# ESP.net
KiCad netlist of a schematic drawn in EAGLE
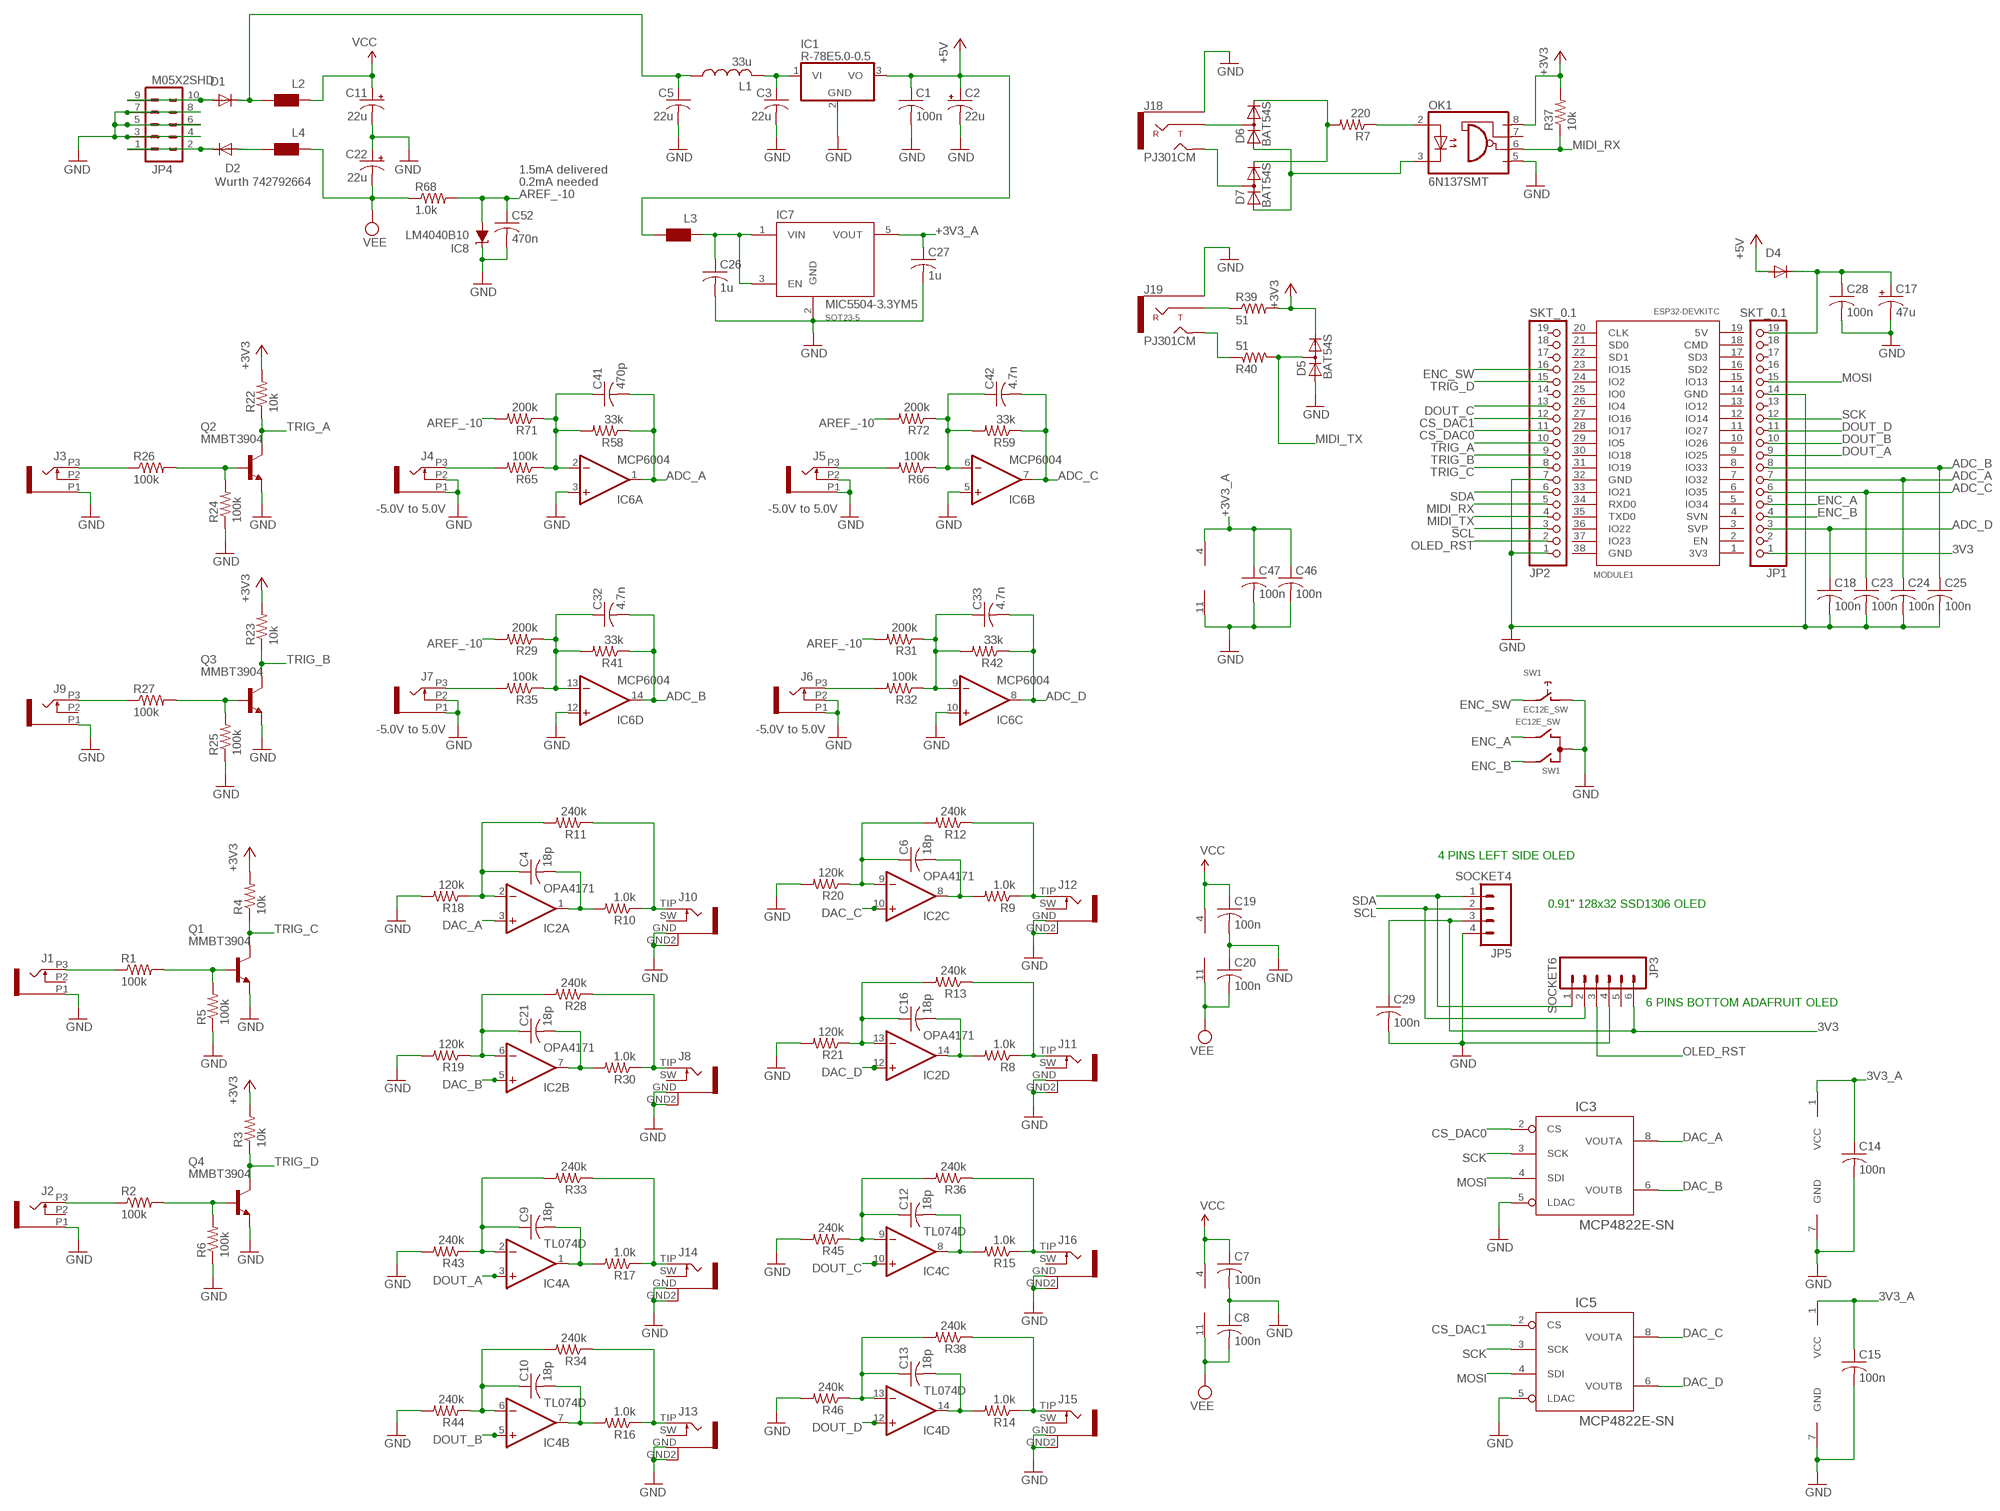
[diagram p0: schematic, sheet 1]

(export (version "E")
  (design (tool "Eeschema 10.0.6"))
  (components
    (comp (ref "C1")
      (value "100n")
      (footprint "eagle-import:C0402")
      (libsource (lib "eagle-import") (part "C-USC0402"))
    )
    (comp (ref "C2")
      (value "22u")
      (footprint "eagle-import:PANASONIC_C")
      (libsource (lib "eagle-import") (part "CPOL-USC"))
    )
    (comp (ref "C3")
      (value "22u")
      (footprint "eagle-import:C1206")
      (libsource (lib "eagle-import") (part "C-USC1206"))
    )
    (comp (ref "C4")
      (value "18p")
      (footprint "eagle-import:C0603")
      (libsource (lib "eagle-import") (part "C-USC0603"))
    )
    (comp (ref "C5")
      (value "22u")
      (footprint "eagle-import:C1206")
      (libsource (lib "eagle-import") (part "C-USC1206"))
    )
    (comp (ref "C6")
      (value "18p")
      (footprint "eagle-import:C0603")
      (libsource (lib "eagle-import") (part "C-USC0603"))
    )
    (comp (ref "C7")
      (value "100n")
      (footprint "eagle-import:C0603")
      (libsource (lib "eagle-import") (part "C-USC0603"))
    )
    (comp (ref "C8")
      (value "100n")
      (footprint "eagle-import:C0603")
      (libsource (lib "eagle-import") (part "C-USC0603"))
    )
    (comp (ref "C9")
      (value "18p")
      (footprint "eagle-import:C0603")
      (libsource (lib "eagle-import") (part "C-USC0603"))
    )
    (comp (ref "C10")
      (value "18p")
      (footprint "eagle-import:C0603")
      (libsource (lib "eagle-import") (part "C-USC0603"))
    )
    (comp (ref "C11")
      (value "22u")
      (footprint "eagle-import:PANASONIC_C")
      (libsource (lib "eagle-import") (part "CPOL-USC"))
    )
    (comp (ref "C12")
      (value "18p")
      (footprint "eagle-import:C0603")
      (libsource (lib "eagle-import") (part "C-USC0603"))
    )
    (comp (ref "C13")
      (value "18p")
      (footprint "eagle-import:C0603")
      (libsource (lib "eagle-import") (part "C-USC0603"))
    )
    (comp (ref "C14")
      (value "100n")
      (footprint "eagle-import:C0603")
      (libsource (lib "eagle-import") (part "C-USC0603"))
    )
    (comp (ref "C15")
      (value "100n")
      (footprint "eagle-import:C0603")
      (libsource (lib "eagle-import") (part "C-USC0603"))
    )
    (comp (ref "C16")
      (value "18p")
      (footprint "eagle-import:C0603")
      (libsource (lib "eagle-import") (part "C-USC0603"))
    )
    (comp (ref "C17")
      (value "47u")
      (footprint "eagle-import:PANASONIC_D")
      (libsource (lib "eagle-import") (part "CPOL-USD"))
    )
    (comp (ref "C18")
      (value "100n")
      (footprint "eagle-import:C0402")
      (libsource (lib "eagle-import") (part "C-USC0402"))
    )
    (comp (ref "C19")
      (value "100n")
      (footprint "eagle-import:C0603")
      (libsource (lib "eagle-import") (part "C-USC0603"))
    )
    (comp (ref "C20")
      (value "100n")
      (footprint "eagle-import:C0603")
      (libsource (lib "eagle-import") (part "C-USC0603"))
    )
    (comp (ref "C21")
      (value "18p")
      (footprint "eagle-import:C0603")
      (libsource (lib "eagle-import") (part "C-USC0603"))
    )
    (comp (ref "C22")
      (value "22u")
      (footprint "eagle-import:PANASONIC_C")
      (libsource (lib "eagle-import") (part "CPOL-USC"))
    )
    (comp (ref "C23")
      (value "100n")
      (footprint "eagle-import:C0402")
      (libsource (lib "eagle-import") (part "C-USC0402"))
    )
    (comp (ref "C24")
      (value "100n")
      (footprint "eagle-import:C0402")
      (libsource (lib "eagle-import") (part "C-USC0402"))
    )
    (comp (ref "C25")
      (value "100n")
      (footprint "eagle-import:C0402")
      (libsource (lib "eagle-import") (part "C-USC0402"))
    )
    (comp (ref "C26")
      (value "1u")
      (footprint "eagle-import:C0603")
      (libsource (lib "eagle-import") (part "C-USC0603"))
    )
    (comp (ref "C27")
      (value "1u")
      (footprint "eagle-import:C0603")
      (libsource (lib "eagle-import") (part "C-USC0603"))
    )
    (comp (ref "C28")
      (value "100n")
      (footprint "eagle-import:C0402")
      (libsource (lib "eagle-import") (part "C-USC0402"))
    )
    (comp (ref "C29")
      (value "100n")
      (footprint "eagle-import:C0603")
      (libsource (lib "eagle-import") (part "C-USC0603"))
    )
    (comp (ref "C32")
      (value "4.7n")
      (footprint "eagle-import:C0402")
      (libsource (lib "eagle-import") (part "C-USC0402"))
    )
    (comp (ref "C33")
      (value "4.7n")
      (footprint "eagle-import:C0402")
      (libsource (lib "eagle-import") (part "C-USC0402"))
    )
    (comp (ref "C41")
      (value "470p")
      (footprint "eagle-import:C0402")
      (libsource (lib "eagle-import") (part "C-USC0402"))
    )
    (comp (ref "C42")
      (value "4.7n")
      (footprint "eagle-import:C0402")
      (libsource (lib "eagle-import") (part "C-USC0402"))
    )
    (comp (ref "C46")
      (value "100n")
      (footprint "eagle-import:C0402")
      (libsource (lib "eagle-import") (part "C-USC0402"))
    )
    (comp (ref "C47")
      (value "100n")
      (footprint "eagle-import:C0402")
      (libsource (lib "eagle-import") (part "C-USC0402"))
    )
    (comp (ref "C52")
      (value "470n")
      (footprint "eagle-import:C0402")
      (libsource (lib "eagle-import") (part "C-USC0402"))
    )
    (comp (ref "D1")
      (value "1N5819HW")
      (footprint "eagle-import:SOD123")
      (libsource (lib "eagle-import") (part "DIODE-SOD123"))
    )
    (comp (ref "D2")
      (value "1N5819HW")
      (footprint "eagle-import:SOD123")
      (libsource (lib "eagle-import") (part "DIODE-SOD123"))
    )
    (comp (ref "D4")
      (value "1N5819HW")
      (footprint "eagle-import:SOD123")
      (libsource (lib "eagle-import") (part "DIODE-SOD123"))
    )
    (comp (ref "D5")
      (value "BAT54S")
      (footprint "eagle-import:SOT23")
      (libsource (lib "eagle-import") (part "DIODE_2CACA-SOT23"))
    )
    (comp (ref "D6")
      (value "BAT54S")
      (footprint "eagle-import:SOT23")
      (libsource (lib "eagle-import") (part "DIODE_2CACA-SOT23"))
    )
    (comp (ref "D7")
      (value "BAT54S")
      (footprint "eagle-import:SOT23")
      (libsource (lib "eagle-import") (part "DIODE_2CACA-SOT23"))
    )
    (comp (ref "IC1")
      (value "R-78E5.0-0.5")
      (footprint "eagle-import:WE78")
      (libsource (lib "eagle-import") (part "WE173950378"))
    )
    (comp (ref "IC2")
      (value "OPA4171")
      (footprint "eagle-import:SO14")
      (libsource (lib "eagle-import") (part "TL074D"))
    )
    (comp (ref "IC3")
      (value "MCP4822E-SN")
      (footprint "eagle-import:SOIC-8")
      (libsource (lib "eagle-import") (part "MCP42E-SN82"))
    )
    (comp (ref "IC4")
      (value "TL074D")
      (footprint "eagle-import:SO14")
      (libsource (lib "eagle-import") (part "TL074D"))
    )
    (comp (ref "IC5")
      (value "MCP4822E-SN")
      (footprint "eagle-import:SOIC-8")
      (libsource (lib "eagle-import") (part "MCP42E-SN82"))
    )
    (comp (ref "IC6")
      (value "MCP6004")
      (footprint "eagle-import:TSSOP14_065")
      (libsource (lib "eagle-import") (part "TL074PW"))
    )
    (comp (ref "IC7")
      (value "MIC5504-3.3YM5")
      (footprint "eagle-import:SOT23-5-DBV")
      (libsource (lib "eagle-import") (part "MIC550X-YM5"))
    )
    (comp (ref "IC8")
      (value "LM4040B10")
      (footprint "eagle-import:DBZ_R-PDSO-G3")
      (fields (field (name "MPN") "LM4041B12IDBZR"))
      (libsource (lib "eagle-import") (part "LM4041DBZB12"))
    )
    (comp (ref "J1")
      (value "PJ301_THONKICONN6")
      (footprint "eagle-import:WQP_PJ_301M6")
      (libsource (lib "eagle-import") (part "PJ301_THONKICONN6"))
    )
    (comp (ref "J2")
      (value "PJ301_THONKICONN6")
      (footprint "eagle-import:WQP_PJ_301M6")
      (libsource (lib "eagle-import") (part "PJ301_THONKICONN6"))
    )
    (comp (ref "J3")
      (value "PJ301_THONKICONN6")
      (footprint "eagle-import:WQP_PJ_301M6")
      (libsource (lib "eagle-import") (part "PJ301_THONKICONN6"))
    )
    (comp (ref "J4")
      (value "PJ301_THONKICONN6")
      (footprint "eagle-import:WQP_PJ_301M6")
      (libsource (lib "eagle-import") (part "PJ301_THONKICONN6"))
    )
    (comp (ref "J5")
      (value "PJ301_THONKICONN6")
      (footprint "eagle-import:WQP_PJ_301M6")
      (libsource (lib "eagle-import") (part "PJ301_THONKICONN6"))
    )
    (comp (ref "J6")
      (value "PJ301_THONKICONN6")
      (footprint "eagle-import:WQP_PJ_301M6")
      (libsource (lib "eagle-import") (part "PJ301_THONKICONN6"))
    )
    (comp (ref "J7")
      (value "PJ301_THONKICONN6")
      (footprint "eagle-import:WQP_PJ_301M6")
      (libsource (lib "eagle-import") (part "PJ301_THONKICONN6"))
    )
    (comp (ref "J8")
      (value "PJ301WQP")
      (footprint "eagle-import:WQP_PJ_301BM")
      (libsource (lib "eagle-import") (part "PJ301WQP"))
    )
    (comp (ref "J9")
      (value "PJ301_THONKICONN6")
      (footprint "eagle-import:WQP_PJ_301M6")
      (libsource (lib "eagle-import") (part "PJ301_THONKICONN6"))
    )
    (comp (ref "J10")
      (value "PJ301WQP")
      (footprint "eagle-import:WQP_PJ_301BM")
      (libsource (lib "eagle-import") (part "PJ301WQP"))
    )
    (comp (ref "J11")
      (value "PJ301WQP")
      (footprint "eagle-import:WQP_PJ_301BM")
      (libsource (lib "eagle-import") (part "PJ301WQP"))
    )
    (comp (ref "J12")
      (value "PJ301WQP")
      (footprint "eagle-import:WQP_PJ_301BM")
      (libsource (lib "eagle-import") (part "PJ301WQP"))
    )
    (comp (ref "J13")
      (value "PJ301WQP")
      (footprint "eagle-import:WQP_PJ_301BM")
      (libsource (lib "eagle-import") (part "PJ301WQP"))
    )
    (comp (ref "J14")
      (value "PJ301WQP")
      (footprint "eagle-import:WQP_PJ_301BM")
      (libsource (lib "eagle-import") (part "PJ301WQP"))
    )
    (comp (ref "J15")
      (value "PJ301WQP")
      (footprint "eagle-import:WQP_PJ_301BM")
      (libsource (lib "eagle-import") (part "PJ301WQP"))
    )
    (comp (ref "J16")
      (value "PJ301WQP")
      (footprint "eagle-import:WQP_PJ_301BM")
      (libsource (lib "eagle-import") (part "PJ301WQP"))
    )
    (comp (ref "J18")
      (value "PJ301CM")
      (footprint "eagle-import:PJ301CM")
      (libsource (lib "eagle-import") (part "PJ301CM"))
    )
    (comp (ref "J19")
      (value "PJ301CM")
      (footprint "eagle-import:PJ301CM")
      (libsource (lib "eagle-import") (part "PJ301CM"))
    )
    (comp (ref "JP1")
      (value "SKT_0.1")
      (footprint "eagle-import:1X19")
      (libsource (lib "eagle-import") (part "PINHD-1X19"))
    )
    (comp (ref "JP2")
      (value "SKT_0.1")
      (footprint "eagle-import:1X19")
      (libsource (lib "eagle-import") (part "PINHD-1X19"))
    )
    (comp (ref "JP3")
      (value "SOCKET6")
      (footprint "eagle-import:MOLEX-1X6-RA")
      (libsource (lib "eagle-import") (part "M06RA"))
    )
    (comp (ref "JP4")
      (value "M05X2SHD")
      (footprint "eagle-import:2X5-SHROUDED")
      (libsource (lib "eagle-import") (part "M05X2SHD"))
    )
    (comp (ref "JP5")
      (value "SOCKET4")
      (footprint "eagle-import:1X04")
      (libsource (lib "eagle-import") (part "M04PTH"))
    )
    (comp (ref "L1")
      (value "33u")
      (footprint "eagle-import:L2012C")
      (libsource (lib "eagle-import") (part "L-USL2012C"))
    )
    (comp (ref "L2")
      (value "WE-CBF_0603")
      (footprint "eagle-import:0603")
      (libsource (lib "eagle-import") (part "WE-CBF_0603"))
    )
    (comp (ref "L3")
      (value "WE-CBF_0603")
      (footprint "eagle-import:0603")
      (libsource (lib "eagle-import") (part "WE-CBF_0603"))
    )
    (comp (ref "L4")
      (value "WE-CBF_0603")
      (footprint "eagle-import:0603")
      (libsource (lib "eagle-import") (part "WE-CBF_0603"))
    )
    (comp (ref "MODULE1")
      (value "ESP32DEVKITC")
      (footprint "eagle-import:ESP32-DEVKITC")
      (libsource (lib "eagle-import") (part "ESP32DEVKITC"))
    )
    (comp (ref "OK1")
      (value "6N137SMT")
      (footprint "eagle-import:DIL8-SMD")
      (libsource (lib "eagle-import") (part "6N137SMT"))
    )
    (comp (ref "Q1")
      (value "MMBT3904")
      (footprint "eagle-import:SOT23-BEC")
      (libsource (lib "eagle-import") (part "-NPN-SOT23-BECMMBT3904LT1"))
    )
    (comp (ref "Q2")
      (value "MMBT3904")
      (footprint "eagle-import:SOT23-BEC")
      (libsource (lib "eagle-import") (part "-NPN-SOT23-BECMMBT3904LT1"))
    )
    (comp (ref "Q3")
      (value "MMBT3904")
      (footprint "eagle-import:SOT23-BEC")
      (libsource (lib "eagle-import") (part "-NPN-SOT23-BECMMBT3904LT1"))
    )
    (comp (ref "Q4")
      (value "MMBT3904")
      (footprint "eagle-import:SOT23-BEC")
      (libsource (lib "eagle-import") (part "-NPN-SOT23-BECMMBT3904LT1"))
    )
    (comp (ref "R1")
      (value "100k")
      (footprint "eagle-import:R0402")
      (libsource (lib "eagle-import") (part "R-US_R0402"))
    )
    (comp (ref "R2")
      (value "100k")
      (footprint "eagle-import:R0402")
      (libsource (lib "eagle-import") (part "R-US_R0402"))
    )
    (comp (ref "R3")
      (value "10k")
      (footprint "eagle-import:R0402")
      (libsource (lib "eagle-import") (part "R-US_R0402"))
    )
    (comp (ref "R4")
      (value "10k")
      (footprint "eagle-import:R0402")
      (libsource (lib "eagle-import") (part "R-US_R0402"))
    )
    (comp (ref "R5")
      (value "100k")
      (footprint "eagle-import:R0402")
      (libsource (lib "eagle-import") (part "R-US_R0402"))
    )
    (comp (ref "R6")
      (value "100k")
      (footprint "eagle-import:R0402")
      (libsource (lib "eagle-import") (part "R-US_R0402"))
    )
    (comp (ref "R7")
      (value "220")
      (footprint "eagle-import:R0603")
      (libsource (lib "eagle-import") (part "R-US_R0603"))
    )
    (comp (ref "R8")
      (value "1.0k")
      (footprint "eagle-import:R0603")
      (libsource (lib "eagle-import") (part "R-US_R0603"))
    )
    (comp (ref "R9")
      (value "1.0k")
      (footprint "eagle-import:R0603")
      (libsource (lib "eagle-import") (part "R-US_R0603"))
    )
    (comp (ref "R10")
      (value "1.0k")
      (footprint "eagle-import:R0603")
      (libsource (lib "eagle-import") (part "R-US_R0603"))
    )
    (comp (ref "R11")
      (value "240k")
      (footprint "eagle-import:R0603")
      (libsource (lib "eagle-import") (part "R-US_R0603"))
    )
    (comp (ref "R12")
      (value "240k")
      (footprint "eagle-import:R0603")
      (libsource (lib "eagle-import") (part "R-US_R0603"))
    )
    (comp (ref "R13")
      (value "240k")
      (footprint "eagle-import:R0603")
      (libsource (lib "eagle-import") (part "R-US_R0603"))
    )
    (comp (ref "R14")
      (value "1.0k")
      (footprint "eagle-import:R0603")
      (libsource (lib "eagle-import") (part "R-US_R0603"))
    )
    (comp (ref "R15")
      (value "1.0k")
      (footprint "eagle-import:R0603")
      (libsource (lib "eagle-import") (part "R-US_R0603"))
    )
    (comp (ref "R16")
      (value "1.0k")
      (footprint "eagle-import:R0603")
      (libsource (lib "eagle-import") (part "R-US_R0603"))
    )
    (comp (ref "R17")
      (value "1.0k")
      (footprint "eagle-import:R0603")
      (libsource (lib "eagle-import") (part "R-US_R0603"))
    )
    (comp (ref "R18")
      (value "120k")
      (footprint "eagle-import:R0603")
      (libsource (lib "eagle-import") (part "R-US_R0603"))
    )
    (comp (ref "R19")
      (value "120k")
      (footprint "eagle-import:R0603")
      (libsource (lib "eagle-import") (part "R-US_R0603"))
    )
    (comp (ref "R20")
      (value "120k")
      (footprint "eagle-import:R0603")
      (libsource (lib "eagle-import") (part "R-US_R0603"))
    )
    (comp (ref "R21")
      (value "120k")
      (footprint "eagle-import:R0603")
      (libsource (lib "eagle-import") (part "R-US_R0603"))
    )
    (comp (ref "R22")
      (value "10k")
      (footprint "eagle-import:R0402")
      (libsource (lib "eagle-import") (part "R-US_R0402"))
    )
    (comp (ref "R23")
      (value "10k")
      (footprint "eagle-import:R0402")
      (libsource (lib "eagle-import") (part "R-US_R0402"))
    )
    (comp (ref "R24")
      (value "100k")
      (footprint "eagle-import:R0402")
      (libsource (lib "eagle-import") (part "R-US_R0402"))
    )
    (comp (ref "R25")
      (value "100k")
      (footprint "eagle-import:R0402")
      (libsource (lib "eagle-import") (part "R-US_R0402"))
    )
    (comp (ref "R26")
      (value "100k")
      (footprint "eagle-import:R0402")
      (libsource (lib "eagle-import") (part "R-US_R0402"))
    )
    (comp (ref "R27")
      (value "100k")
      (footprint "eagle-import:R0402")
      (libsource (lib "eagle-import") (part "R-US_R0402"))
    )
    (comp (ref "R28")
      (value "240k")
      (footprint "eagle-import:R0603")
      (libsource (lib "eagle-import") (part "R-US_R0603"))
    )
    (comp (ref "R29")
      (value "200k")
      (footprint "eagle-import:R0402")
      (libsource (lib "eagle-import") (part "R-US_R0402"))
    )
    (comp (ref "R30")
      (value "1.0k")
      (footprint "eagle-import:R0603")
      (libsource (lib "eagle-import") (part "R-US_R0603"))
    )
    (comp (ref "R31")
      (value "200k")
      (footprint "eagle-import:R0402")
      (libsource (lib "eagle-import") (part "R-US_R0402"))
    )
    (comp (ref "R32")
      (value "100k")
      (footprint "eagle-import:R0402")
      (libsource (lib "eagle-import") (part "R-US_R0402"))
    )
    (comp (ref "R33")
      (value "240k")
      (footprint "eagle-import:R0603")
      (libsource (lib "eagle-import") (part "R-US_R0603"))
    )
    (comp (ref "R34")
      (value "240k")
      (footprint "eagle-import:R0603")
      (libsource (lib "eagle-import") (part "R-US_R0603"))
    )
    (comp (ref "R35")
      (value "100k")
      (footprint "eagle-import:R0402")
      (libsource (lib "eagle-import") (part "R-US_R0402"))
    )
    (comp (ref "R36")
      (value "240k")
      (footprint "eagle-import:R0603")
      (libsource (lib "eagle-import") (part "R-US_R0603"))
    )
    (comp (ref "R37")
      (value "10k")
      (footprint "eagle-import:R0603")
      (libsource (lib "eagle-import") (part "R-US_R0603"))
    )
    (comp (ref "R38")
      (value "240k")
      (footprint "eagle-import:R0603")
      (libsource (lib "eagle-import") (part "R-US_R0603"))
    )
    (comp (ref "R39")
      (value "51")
      (footprint "eagle-import:R0603")
      (libsource (lib "eagle-import") (part "R-US_R0603"))
    )
    (comp (ref "R40")
      (value "51")
      (footprint "eagle-import:R0603")
      (libsource (lib "eagle-import") (part "R-US_R0603"))
    )
    (comp (ref "R41")
      (value "33k")
      (footprint "eagle-import:R0402")
      (libsource (lib "eagle-import") (part "R-US_R0402"))
    )
    (comp (ref "R42")
      (value "33k")
      (footprint "eagle-import:R0402")
      (libsource (lib "eagle-import") (part "R-US_R0402"))
    )
    (comp (ref "R43")
      (value "240k")
      (footprint "eagle-import:R0603")
      (libsource (lib "eagle-import") (part "R-US_R0603"))
    )
    (comp (ref "R44")
      (value "240k")
      (footprint "eagle-import:R0603")
      (libsource (lib "eagle-import") (part "R-US_R0603"))
    )
    (comp (ref "R45")
      (value "240k")
      (footprint "eagle-import:R0603")
      (libsource (lib "eagle-import") (part "R-US_R0603"))
    )
    (comp (ref "R46")
      (value "240k")
      (footprint "eagle-import:R0603")
      (libsource (lib "eagle-import") (part "R-US_R0603"))
    )
    (comp (ref "R58")
      (value "33k")
      (footprint "eagle-import:R0402")
      (libsource (lib "eagle-import") (part "R-US_R0402"))
    )
    (comp (ref "R59")
      (value "33k")
      (footprint "eagle-import:R0402")
      (libsource (lib "eagle-import") (part "R-US_R0402"))
    )
    (comp (ref "R65")
      (value "100k")
      (footprint "eagle-import:R0402")
      (libsource (lib "eagle-import") (part "R-US_R0402"))
    )
    (comp (ref "R66")
      (value "100k")
      (footprint "eagle-import:R0402")
      (libsource (lib "eagle-import") (part "R-US_R0402"))
    )
    (comp (ref "R68")
      (value "1.0k")
      (footprint "eagle-import:R0402")
      (libsource (lib "eagle-import") (part "R-US_R0402"))
    )
    (comp (ref "R71")
      (value "200k")
      (footprint "eagle-import:R0402")
      (libsource (lib "eagle-import") (part "R-US_R0402"))
    )
    (comp (ref "R72")
      (value "200k")
      (footprint "eagle-import:R0402")
      (libsource (lib "eagle-import") (part "R-US_R0402"))
    )
    (comp (ref "SW1")
      (value "EC12E_SW")
      (footprint "eagle-import:ALPS_EC12E_SW")
      (libsource (lib "eagle-import") (part "EC12E_SW"))
    )
  )
  (nets
    (net (code "1") (name "+3V3") (class "Default")
      (node (ref "D5") (pin "2") (pinfunction "C_2") (pintype "passive"))
      (node (ref "OK1") (pin "8") (pinfunction "VCC_8") (pintype "passive"))
      (node (ref "R22") (pin "2") (pinfunction "2_2") (pintype "passive"))
      (node (ref "R23") (pin "2") (pinfunction "2_2") (pintype "passive"))
      (node (ref "R3") (pin "2") (pinfunction "2_2") (pintype "passive"))
      (node (ref "R37") (pin "2") (pinfunction "2_2") (pintype "passive"))
      (node (ref "R39") (pin "2") (pinfunction "2_2") (pintype "passive"))
      (node (ref "R4") (pin "2") (pinfunction "2_2") (pintype "passive"))
    )
    (net (code "2") (name "+5V") (class "Default")
      (node (ref "C1") (pin "1") (pinfunction "1_1") (pintype "passive"))
      (node (ref "C2") (pin "+") (pinfunction "+_+") (pintype "passive"))
      (node (ref "D4") (pin "A") (pinfunction "A_A") (pintype "passive"))
      (node (ref "IC1") (pin "3") (pinfunction "VO_3") (pintype "passive"))
      (node (ref "L3") (pin "2") (pinfunction "2_2") (pintype "passive"))
    )
    (net (code "3") (name "/+3V3_A") (class "Default")
      (node (ref "C27") (pin "1") (pinfunction "1_1") (pintype "passive"))
      (node (ref "C46") (pin "1") (pinfunction "1_1") (pintype "passive"))
      (node (ref "C47") (pin "1") (pinfunction "1_1") (pintype "passive"))
      (node (ref "IC6") (pin "4") (pinfunction "V+_4") (pintype "power_in"))
      (node (ref "IC7") (pin "5") (pinfunction "VOUT_5") (pintype "bidirectional"))
    )
    (net (code "4") (name "/3V3") (class "Default")
      (node (ref "C29") (pin "1") (pinfunction "1_1") (pintype "passive"))
      (node (ref "JP1") (pin "1") (pinfunction "1_1") (pintype "passive"))
      (node (ref "JP3") (pin "6") (pinfunction "6_6") (pintype "passive"))
      (node (ref "JP5") (pin "3") (pinfunction "3_3") (pintype "passive"))
    )
    (net (code "5") (name "/3V3_A") (class "Default")
      (node (ref "C14") (pin "1") (pinfunction "1_1") (pintype "passive"))
      (node (ref "C15") (pin "1") (pinfunction "1_1") (pintype "passive"))
      (node (ref "IC3") (pin "1") (pinfunction "VCC_1") (pintype "power_in"))
      (node (ref "IC5") (pin "1") (pinfunction "VCC_1") (pintype "power_in"))
    )
    (net (code "6") (name "/ADC_A") (class "Default")
      (node (ref "C24") (pin "1") (pinfunction "1_1") (pintype "passive"))
      (node (ref "C41") (pin "2") (pinfunction "2_2") (pintype "passive"))
      (node (ref "IC6") (pin "1") (pinfunction "OUT_1") (pintype "output"))
      (node (ref "JP1") (pin "7") (pinfunction "7_7") (pintype "passive"))
      (node (ref "R58") (pin "1") (pinfunction "1_1") (pintype "passive"))
    )
    (net (code "7") (name "/ADC_B") (class "Default")
      (node (ref "C25") (pin "1") (pinfunction "1_1") (pintype "passive"))
      (node (ref "C32") (pin "2") (pinfunction "2_2") (pintype "passive"))
      (node (ref "IC6") (pin "14") (pinfunction "OUT_14") (pintype "output"))
      (node (ref "JP1") (pin "8") (pinfunction "8_8") (pintype "passive"))
      (node (ref "R41") (pin "1") (pinfunction "1_1") (pintype "passive"))
    )
    (net (code "8") (name "/ADC_C") (class "Default")
      (node (ref "C23") (pin "1") (pinfunction "1_1") (pintype "passive"))
      (node (ref "C42") (pin "2") (pinfunction "2_2") (pintype "passive"))
      (node (ref "IC6") (pin "7") (pinfunction "OUT_7") (pintype "output"))
      (node (ref "JP1") (pin "6") (pinfunction "6_6") (pintype "passive"))
      (node (ref "R59") (pin "1") (pinfunction "1_1") (pintype "passive"))
    )
    (net (code "9") (name "/ADC_D") (class "Default")
      (node (ref "C18") (pin "1") (pinfunction "1_1") (pintype "passive"))
      (node (ref "C33") (pin "2") (pinfunction "2_2") (pintype "passive"))
      (node (ref "IC6") (pin "8") (pinfunction "OUT_8") (pintype "output"))
      (node (ref "JP1") (pin "3") (pinfunction "3_3") (pintype "passive"))
      (node (ref "R42") (pin "1") (pinfunction "1_1") (pintype "passive"))
    )
    (net (code "10") (name "/AREF_-10") (class "Default")
      (node (ref "C52") (pin "1") (pinfunction "1_1") (pintype "passive"))
      (node (ref "IC8") (pin "2") (pinfunction "A_2") (pintype "passive"))
      (node (ref "R29") (pin "2") (pinfunction "2_2") (pintype "passive"))
      (node (ref "R31") (pin "2") (pinfunction "2_2") (pintype "passive"))
      (node (ref "R68") (pin "2") (pinfunction "2_2") (pintype "passive"))
      (node (ref "R71") (pin "2") (pinfunction "2_2") (pintype "passive"))
      (node (ref "R72") (pin "2") (pinfunction "2_2") (pintype "passive"))
    )
    (net (code "11") (name "/CS_DAC0") (class "Default")
      (node (ref "IC3") (pin "2") (pinfunction "CS_2") (pintype "input"))
      (node (ref "JP2") (pin "11") (pinfunction "11_11") (pintype "passive"))
    )
    (net (code "12") (name "/CS_DAC1") (class "Default")
      (node (ref "IC5") (pin "2") (pinfunction "CS_2") (pintype "input"))
      (node (ref "JP2") (pin "12") (pinfunction "12_12") (pintype "passive"))
    )
    (net (code "13") (name "/DAC_A") (class "Default")
      (node (ref "IC2") (pin "3") (pinfunction "+IN_3") (pintype "input"))
      (node (ref "IC3") (pin "8") (pinfunction "VOUTA_8") (pintype "output"))
    )
    (net (code "14") (name "/DAC_B") (class "Default")
      (node (ref "IC2") (pin "5") (pinfunction "+IN_5") (pintype "input"))
      (node (ref "IC3") (pin "6") (pinfunction "VOUTB_6") (pintype "output"))
    )
    (net (code "15") (name "/DAC_C") (class "Default")
      (node (ref "IC2") (pin "10") (pinfunction "+IN_10") (pintype "input"))
      (node (ref "IC5") (pin "8") (pinfunction "VOUTA_8") (pintype "output"))
    )
    (net (code "16") (name "/DAC_D") (class "Default")
      (node (ref "IC2") (pin "12") (pinfunction "+IN_12") (pintype "input"))
      (node (ref "IC5") (pin "6") (pinfunction "VOUTB_6") (pintype "output"))
    )
    (net (code "17") (name "/DOUT_A") (class "Default")
      (node (ref "IC4") (pin "3") (pinfunction "+IN_3") (pintype "input"))
      (node (ref "JP1") (pin "9") (pinfunction "9_9") (pintype "passive"))
    )
    (net (code "18") (name "/DOUT_B") (class "Default")
      (node (ref "IC4") (pin "5") (pinfunction "+IN_5") (pintype "input"))
      (node (ref "JP1") (pin "10") (pinfunction "10_10") (pintype "passive"))
    )
    (net (code "19") (name "/DOUT_C") (class "Default")
      (node (ref "IC4") (pin "10") (pinfunction "+IN_10") (pintype "input"))
      (node (ref "JP2") (pin "13") (pinfunction "13_13") (pintype "passive"))
    )
    (net (code "20") (name "/DOUT_D") (class "Default")
      (node (ref "IC4") (pin "12") (pinfunction "+IN_12") (pintype "input"))
      (node (ref "JP1") (pin "11") (pinfunction "11_11") (pintype "passive"))
    )
    (net (code "21") (name "/ENC_A") (class "Default")
      (node (ref "JP1") (pin "5") (pinfunction "5_5") (pintype "passive"))
      (node (ref "SW1") (pin "B") (pinfunction "B_B") (pintype "passive"))
    )
    (net (code "22") (name "/ENC_B") (class "Default")
      (node (ref "JP1") (pin "4") (pinfunction "4_4") (pintype "passive"))
      (node (ref "SW1") (pin "A") (pinfunction "A_A") (pintype "passive"))
    )
    (net (code "23") (name "/ENC_SW") (class "Default")
      (node (ref "JP2") (pin "16") (pinfunction "16_16") (pintype "passive"))
      (node (ref "SW1") (pin "E") (pinfunction "2_E") (pintype "passive"))
    )
    (net (code "24") (name "/MIDI_RX") (class "Default")
      (node (ref "JP2") (pin "5") (pinfunction "5_5") (pintype "passive"))
      (node (ref "OK1") (pin "6") (pinfunction "VO_6") (pintype "passive"))
      (node (ref "R37") (pin "1") (pinfunction "1_1") (pintype "passive"))
    )
    (net (code "25") (name "/MIDI_TX") (class "Default")
      (node (ref "D5") (pin "3") (pinfunction "AC_3") (pintype "passive"))
      (node (ref "JP2") (pin "4") (pinfunction "4_4") (pintype "passive"))
      (node (ref "R40") (pin "2") (pinfunction "2_2") (pintype "passive"))
    )
    (net (code "26") (name "/MOSI") (class "Default")
      (node (ref "IC3") (pin "4") (pinfunction "SDI_4") (pintype "input"))
      (node (ref "IC5") (pin "4") (pinfunction "SDI_4") (pintype "input"))
      (node (ref "JP1") (pin "15") (pinfunction "15_15") (pintype "passive"))
    )
    (net (code "27") (name "/OLED_RST") (class "Default")
      (node (ref "JP2") (pin "2") (pinfunction "2_2") (pintype "passive"))
      (node (ref "JP3") (pin "3") (pinfunction "3_3") (pintype "passive"))
    )
    (net (code "28") (name "/SCK") (class "Default")
      (node (ref "IC3") (pin "3") (pinfunction "SCK_3") (pintype "input"))
      (node (ref "IC5") (pin "3") (pinfunction "SCK_3") (pintype "input"))
      (node (ref "JP1") (pin "12") (pinfunction "12_12") (pintype "passive"))
    )
    (net (code "29") (name "/SCL") (class "Default")
      (node (ref "JP2") (pin "3") (pinfunction "3_3") (pintype "passive"))
      (node (ref "JP3") (pin "2") (pinfunction "2_2") (pintype "passive"))
      (node (ref "JP5") (pin "2") (pinfunction "2_2") (pintype "passive"))
    )
    (net (code "30") (name "/SDA") (class "Default")
      (node (ref "JP2") (pin "6") (pinfunction "6_6") (pintype "passive"))
      (node (ref "JP3") (pin "1") (pinfunction "1_1") (pintype "passive"))
      (node (ref "JP5") (pin "1") (pinfunction "1_1") (pintype "passive"))
    )
    (net (code "31") (name "/TRIG_A") (class "Default")
      (node (ref "JP2") (pin "10") (pinfunction "10_10") (pintype "passive"))
      (node (ref "Q2") (pin "C") (pinfunction "C_C") (pintype "passive"))
      (node (ref "R22") (pin "1") (pinfunction "1_1") (pintype "passive"))
    )
    (net (code "32") (name "/TRIG_B") (class "Default")
      (node (ref "JP2") (pin "9") (pinfunction "9_9") (pintype "passive"))
      (node (ref "Q3") (pin "C") (pinfunction "C_C") (pintype "passive"))
      (node (ref "R23") (pin "1") (pinfunction "1_1") (pintype "passive"))
    )
    (net (code "33") (name "/TRIG_C") (class "Default")
      (node (ref "JP2") (pin "8") (pinfunction "8_8") (pintype "passive"))
      (node (ref "Q1") (pin "C") (pinfunction "C_C") (pintype "passive"))
      (node (ref "R4") (pin "1") (pinfunction "1_1") (pintype "passive"))
    )
    (net (code "34") (name "/TRIG_D") (class "Default")
      (node (ref "JP2") (pin "15") (pinfunction "15_15") (pintype "passive"))
      (node (ref "Q4") (pin "C") (pinfunction "C_C") (pintype "passive"))
      (node (ref "R3") (pin "1") (pinfunction "1_1") (pintype "passive"))
    )
    (net (code "35") (name "GND") (class "Default")
      (node (ref "C1") (pin "2") (pinfunction "2_2") (pintype "passive"))
      (node (ref "C11") (pin "-") (pinfunction "-_-") (pintype "passive"))
      (node (ref "C14") (pin "2") (pinfunction "2_2") (pintype "passive"))
      (node (ref "C15") (pin "2") (pinfunction "2_2") (pintype "passive"))
      (node (ref "C17") (pin "-") (pinfunction "-_-") (pintype "passive"))
      (node (ref "C18") (pin "2") (pinfunction "2_2") (pintype "passive"))
      (node (ref "C19") (pin "2") (pinfunction "2_2") (pintype "passive"))
      (node (ref "C2") (pin "-") (pinfunction "-_-") (pintype "passive"))
      (node (ref "C20") (pin "1") (pinfunction "1_1") (pintype "passive"))
      (node (ref "C22") (pin "+") (pinfunction "+_+") (pintype "passive"))
      (node (ref "C23") (pin "2") (pinfunction "2_2") (pintype "passive"))
      (node (ref "C24") (pin "2") (pinfunction "2_2") (pintype "passive"))
      (node (ref "C25") (pin "2") (pinfunction "2_2") (pintype "passive"))
      (node (ref "C26") (pin "2") (pinfunction "2_2") (pintype "passive"))
      (node (ref "C27") (pin "2") (pinfunction "2_2") (pintype "passive"))
      (node (ref "C28") (pin "2") (pinfunction "2_2") (pintype "passive"))
      (node (ref "C29") (pin "2") (pinfunction "2_2") (pintype "passive"))
      (node (ref "C3") (pin "2") (pinfunction "2_2") (pintype "passive"))
      (node (ref "C46") (pin "2") (pinfunction "2_2") (pintype "passive"))
      (node (ref "C47") (pin "2") (pinfunction "2_2") (pintype "passive"))
      (node (ref "C5") (pin "2") (pinfunction "2_2") (pintype "passive"))
      (node (ref "C52") (pin "2") (pinfunction "2_2") (pintype "passive"))
      (node (ref "C7") (pin "2") (pinfunction "2_2") (pintype "passive"))
      (node (ref "C8") (pin "1") (pinfunction "1_1") (pintype "passive"))
      (node (ref "D5") (pin "1") (pinfunction "A_1") (pintype "passive"))
      (node (ref "IC1") (pin "2") (pinfunction "GND_2") (pintype "passive"))
      (node (ref "IC3") (pin "5") (pinfunction "LDAC_5") (pintype "input"))
      (node (ref "IC3") (pin "7") (pinfunction "GND_7") (pintype "power_in"))
      (node (ref "IC5") (pin "5") (pinfunction "LDAC_5") (pintype "input"))
      (node (ref "IC5") (pin "7") (pinfunction "GND_7") (pintype "power_in"))
      (node (ref "IC6") (pin "10") (pinfunction "+IN_10") (pintype "input"))
      (node (ref "IC6") (pin "11") (pinfunction "V-_11") (pintype "power_in"))
      (node (ref "IC6") (pin "12") (pinfunction "+IN_12") (pintype "input"))
      (node (ref "IC6") (pin "3") (pinfunction "+IN_3") (pintype "input"))
      (node (ref "IC6") (pin "5") (pinfunction "+IN_5") (pintype "input"))
      (node (ref "IC7") (pin "2") (pinfunction "GND_2") (pintype "bidirectional"))
      (node (ref "IC8") (pin "1") (pinfunction "C_1") (pintype "passive"))
      (node (ref "J1") (pin "P1") (pinfunction "1_P1") (pintype "passive"))
      (node (ref "J10") (pin "GND") (pinfunction "1_GND") (pintype "passive"))
      (node (ref "J10") (pin "GND2") (pinfunction "4_GND2") (pintype "passive"))
      (node (ref "J11") (pin "GND") (pinfunction "1_GND") (pintype "passive"))
      (node (ref "J11") (pin "GND2") (pinfunction "4_GND2") (pintype "passive"))
      (node (ref "J12") (pin "GND") (pinfunction "1_GND") (pintype "passive"))
      (node (ref "J12") (pin "GND2") (pinfunction "4_GND2") (pintype "passive"))
      (node (ref "J13") (pin "GND") (pinfunction "1_GND") (pintype "passive"))
      (node (ref "J13") (pin "GND2") (pinfunction "4_GND2") (pintype "passive"))
      (node (ref "J14") (pin "GND") (pinfunction "1_GND") (pintype "passive"))
      (node (ref "J14") (pin "GND2") (pinfunction "4_GND2") (pintype "passive"))
      (node (ref "J15") (pin "GND") (pinfunction "1_GND") (pintype "passive"))
      (node (ref "J15") (pin "GND2") (pinfunction "4_GND2") (pintype "passive"))
      (node (ref "J16") (pin "GND") (pinfunction "1_GND") (pintype "passive"))
      (node (ref "J16") (pin "GND2") (pinfunction "4_GND2") (pintype "passive"))
      (node (ref "J18") (pin "P$1") (pinfunction "EARTH_P$1") (pintype "bidirectional"))
      (node (ref "J19") (pin "P$1") (pinfunction "EARTH_P$1") (pintype "bidirectional"))
      (node (ref "J2") (pin "P1") (pinfunction "1_P1") (pintype "passive"))
      (node (ref "J3") (pin "P1") (pinfunction "1_P1") (pintype "passive"))
      (node (ref "J4") (pin "P1") (pinfunction "1_P1") (pintype "passive"))
      (node (ref "J4") (pin "P2") (pinfunction "2_P2") (pintype "passive"))
      (node (ref "J5") (pin "P1") (pinfunction "1_P1") (pintype "passive"))
      (node (ref "J5") (pin "P2") (pinfunction "2_P2") (pintype "passive"))
      (node (ref "J6") (pin "P1") (pinfunction "1_P1") (pintype "passive"))
      (node (ref "J6") (pin "P2") (pinfunction "2_P2") (pintype "passive"))
      (node (ref "J7") (pin "P1") (pinfunction "1_P1") (pintype "passive"))
      (node (ref "J7") (pin "P2") (pinfunction "2_P2") (pintype "passive"))
      (node (ref "J8") (pin "GND") (pinfunction "1_GND") (pintype "passive"))
      (node (ref "J8") (pin "GND2") (pinfunction "4_GND2") (pintype "passive"))
      (node (ref "J9") (pin "P1") (pinfunction "1_P1") (pintype "passive"))
      (node (ref "JP1") (pin "14") (pinfunction "14_14") (pintype "passive"))
      (node (ref "JP2") (pin "1") (pinfunction "1_1") (pintype "passive"))
      (node (ref "JP2") (pin "7") (pinfunction "7_7") (pintype "passive"))
      (node (ref "JP3") (pin "4") (pinfunction "4_4") (pintype "passive"))
      (node (ref "JP4") (pin "3") (pinfunction "3_3") (pintype "passive"))
      (node (ref "JP4") (pin "4") (pinfunction "4_4") (pintype "passive"))
      (node (ref "JP4") (pin "5") (pinfunction "5_5") (pintype "passive"))
      (node (ref "JP4") (pin "6") (pinfunction "6_6") (pintype "passive"))
      (node (ref "JP4") (pin "7") (pinfunction "7_7") (pintype "passive"))
      (node (ref "JP4") (pin "8") (pinfunction "8_8") (pintype "passive"))
      (node (ref "JP5") (pin "4") (pinfunction "4_4") (pintype "passive"))
      (node (ref "OK1") (pin "5") (pinfunction "GND_5") (pintype "passive"))
      (node (ref "Q1") (pin "E") (pinfunction "E_E") (pintype "passive"))
      (node (ref "Q2") (pin "E") (pinfunction "E_E") (pintype "passive"))
      (node (ref "Q3") (pin "E") (pinfunction "E_E") (pintype "passive"))
      (node (ref "Q4") (pin "E") (pinfunction "E_E") (pintype "passive"))
      (node (ref "R18") (pin "2") (pinfunction "2_2") (pintype "passive"))
      (node (ref "R19") (pin "2") (pinfunction "2_2") (pintype "passive"))
      (node (ref "R20") (pin "2") (pinfunction "2_2") (pintype "passive"))
      (node (ref "R21") (pin "2") (pinfunction "2_2") (pintype "passive"))
      (node (ref "R24") (pin "1") (pinfunction "1_1") (pintype "passive"))
      (node (ref "R25") (pin "1") (pinfunction "1_1") (pintype "passive"))
      (node (ref "R43") (pin "2") (pinfunction "2_2") (pintype "passive"))
      (node (ref "R44") (pin "2") (pinfunction "2_2") (pintype "passive"))
      (node (ref "R45") (pin "2") (pinfunction "2_2") (pintype "passive"))
      (node (ref "R46") (pin "2") (pinfunction "2_2") (pintype "passive"))
      (node (ref "R5") (pin "1") (pinfunction "1_1") (pintype "passive"))
      (node (ref "R6") (pin "1") (pinfunction "1_1") (pintype "passive"))
      (node (ref "SW1") (pin "C") (pinfunction "C_C") (pintype "passive"))
      (node (ref "SW1") (pin "D") (pinfunction "1_D") (pintype "passive"))
    )
    (net (code "36") (name "Net-(C5-Pad1)") (class "Default")
      (node (ref "C5") (pin "1") (pinfunction "1_1") (pintype "passive"))
      (node (ref "D1") (pin "C") (pinfunction "C_C") (pintype "passive"))
      (node (ref "L1") (pin "1") (pinfunction "1_1") (pintype "passive"))
      (node (ref "L2") (pin "2") (pinfunction "2_2") (pintype "passive"))
    )
    (net (code "37") (name "Net-(C17-Pad+)") (class "Default")
      (node (ref "C17") (pin "+") (pinfunction "+_+") (pintype "passive"))
      (node (ref "C28") (pin "1") (pinfunction "1_1") (pintype "passive"))
      (node (ref "D4") (pin "C") (pinfunction "C_C") (pintype "passive"))
      (node (ref "JP1") (pin "19") (pinfunction "19_19") (pintype "passive"))
    )
    (net (code "38") (name "Net-(D1-PadA)") (class "Default")
      (node (ref "D1") (pin "A") (pinfunction "A_A") (pintype "passive"))
      (node (ref "JP4") (pin "10") (pinfunction "10_10") (pintype "passive"))
      (node (ref "JP4") (pin "9") (pinfunction "9_9") (pintype "passive"))
    )
    (net (code "39") (name "Net-(D2-PadA)") (class "Default")
      (node (ref "D2") (pin "A") (pinfunction "A_A") (pintype "passive"))
      (node (ref "L4") (pin "2") (pinfunction "2_2") (pintype "passive"))
    )
    (net (code "40") (name "Net-(D2-PadC)") (class "Default")
      (node (ref "D2") (pin "C") (pinfunction "C_C") (pintype "passive"))
      (node (ref "JP4") (pin "1") (pinfunction "1_1") (pintype "passive"))
      (node (ref "JP4") (pin "2") (pinfunction "2_2") (pintype "passive"))
    )
    (net (code "41") (name "Net-(D6-A)") (class "Default")
      (node (ref "D6") (pin "1") (pinfunction "A_1") (pintype "passive"))
      (node (ref "D7") (pin "1") (pinfunction "A_1") (pintype "passive"))
      (node (ref "OK1") (pin "3") (pinfunction "C_3") (pintype "passive"))
    )
    (net (code "42") (name "Net-(D6-AC)") (class "Default")
      (node (ref "D6") (pin "3") (pinfunction "AC_3") (pintype "passive"))
      (node (ref "J18") (pin "P$2") (pinfunction "RING_P$2") (pintype "bidirectional"))
    )
    (net (code "43") (name "Net-(D6-C)") (class "Default")
      (node (ref "D6") (pin "2") (pinfunction "C_2") (pintype "passive"))
      (node (ref "D7") (pin "2") (pinfunction "C_2") (pintype "passive"))
      (node (ref "R7") (pin "2") (pinfunction "2_2") (pintype "passive"))
    )
    (net (code "44") (name "Net-(D7-AC)") (class "Default")
      (node (ref "D7") (pin "3") (pinfunction "AC_3") (pintype "passive"))
      (node (ref "J18") (pin "P$3") (pinfunction "TIP_P$3") (pintype "bidirectional"))
    )
    (net (code "45") (name "Net-(IC1-VI)") (class "Default")
      (node (ref "C3") (pin "1") (pinfunction "1_1") (pintype "passive"))
      (node (ref "IC1") (pin "1") (pinfunction "VI_1") (pintype "input"))
      (node (ref "L1") (pin "2") (pinfunction "2_2") (pintype "passive"))
    )
    (net (code "46") (name "Net-(IC2A--IN)") (class "Default")
      (node (ref "C4") (pin "1") (pinfunction "1_1") (pintype "passive"))
      (node (ref "IC2") (pin "2") (pinfunction "-IN_2") (pintype "input"))
      (node (ref "R11") (pin "2") (pinfunction "2_2") (pintype "passive"))
      (node (ref "R18") (pin "1") (pinfunction "1_1") (pintype "passive"))
    )
    (net (code "47") (name "Net-(IC2A-OUT)") (class "Default")
      (node (ref "C4") (pin "2") (pinfunction "2_2") (pintype "passive"))
      (node (ref "IC2") (pin "1") (pinfunction "OUT_1") (pintype "output"))
      (node (ref "R10") (pin "2") (pinfunction "2_2") (pintype "passive"))
    )
    (net (code "48") (name "Net-(IC2B--IN)") (class "Default")
      (node (ref "C21") (pin "1") (pinfunction "1_1") (pintype "passive"))
      (node (ref "IC2") (pin "6") (pinfunction "-IN_6") (pintype "input"))
      (node (ref "R19") (pin "1") (pinfunction "1_1") (pintype "passive"))
      (node (ref "R28") (pin "2") (pinfunction "2_2") (pintype "passive"))
    )
    (net (code "49") (name "Net-(IC2B-OUT)") (class "Default")
      (node (ref "C21") (pin "2") (pinfunction "2_2") (pintype "passive"))
      (node (ref "IC2") (pin "7") (pinfunction "OUT_7") (pintype "output"))
      (node (ref "R30") (pin "2") (pinfunction "2_2") (pintype "passive"))
    )
    (net (code "50") (name "Net-(IC2C--IN)") (class "Default")
      (node (ref "C6") (pin "1") (pinfunction "1_1") (pintype "passive"))
      (node (ref "IC2") (pin "9") (pinfunction "-IN_9") (pintype "input"))
      (node (ref "R12") (pin "2") (pinfunction "2_2") (pintype "passive"))
      (node (ref "R20") (pin "1") (pinfunction "1_1") (pintype "passive"))
    )
    (net (code "51") (name "Net-(IC2C-OUT)") (class "Default")
      (node (ref "C6") (pin "2") (pinfunction "2_2") (pintype "passive"))
      (node (ref "IC2") (pin "8") (pinfunction "OUT_8") (pintype "output"))
      (node (ref "R9") (pin "2") (pinfunction "2_2") (pintype "passive"))
    )
    (net (code "52") (name "Net-(IC2D--IN)") (class "Default")
      (node (ref "C16") (pin "1") (pinfunction "1_1") (pintype "passive"))
      (node (ref "IC2") (pin "13") (pinfunction "-IN_13") (pintype "input"))
      (node (ref "R13") (pin "2") (pinfunction "2_2") (pintype "passive"))
      (node (ref "R21") (pin "1") (pinfunction "1_1") (pintype "passive"))
    )
    (net (code "53") (name "Net-(IC2D-OUT)") (class "Default")
      (node (ref "C16") (pin "2") (pinfunction "2_2") (pintype "passive"))
      (node (ref "IC2") (pin "14") (pinfunction "OUT_14") (pintype "output"))
      (node (ref "R8") (pin "2") (pinfunction "2_2") (pintype "passive"))
    )
    (net (code "54") (name "Net-(IC4A--IN)") (class "Default")
      (node (ref "C9") (pin "1") (pinfunction "1_1") (pintype "passive"))
      (node (ref "IC4") (pin "2") (pinfunction "-IN_2") (pintype "input"))
      (node (ref "R33") (pin "2") (pinfunction "2_2") (pintype "passive"))
      (node (ref "R43") (pin "1") (pinfunction "1_1") (pintype "passive"))
    )
    (net (code "55") (name "Net-(IC4A-OUT)") (class "Default")
      (node (ref "C9") (pin "2") (pinfunction "2_2") (pintype "passive"))
      (node (ref "IC4") (pin "1") (pinfunction "OUT_1") (pintype "output"))
      (node (ref "R17") (pin "2") (pinfunction "2_2") (pintype "passive"))
    )
    (net (code "56") (name "Net-(IC4B--IN)") (class "Default")
      (node (ref "C10") (pin "1") (pinfunction "1_1") (pintype "passive"))
      (node (ref "IC4") (pin "6") (pinfunction "-IN_6") (pintype "input"))
      (node (ref "R34") (pin "2") (pinfunction "2_2") (pintype "passive"))
      (node (ref "R44") (pin "1") (pinfunction "1_1") (pintype "passive"))
    )
    (net (code "57") (name "Net-(IC4B-OUT)") (class "Default")
      (node (ref "C10") (pin "2") (pinfunction "2_2") (pintype "passive"))
      (node (ref "IC4") (pin "7") (pinfunction "OUT_7") (pintype "output"))
      (node (ref "R16") (pin "2") (pinfunction "2_2") (pintype "passive"))
    )
    (net (code "58") (name "Net-(IC4C--IN)") (class "Default")
      (node (ref "C12") (pin "1") (pinfunction "1_1") (pintype "passive"))
      (node (ref "IC4") (pin "9") (pinfunction "-IN_9") (pintype "input"))
      (node (ref "R36") (pin "2") (pinfunction "2_2") (pintype "passive"))
      (node (ref "R45") (pin "1") (pinfunction "1_1") (pintype "passive"))
    )
    (net (code "59") (name "Net-(IC4C-OUT)") (class "Default")
      (node (ref "C12") (pin "2") (pinfunction "2_2") (pintype "passive"))
      (node (ref "IC4") (pin "8") (pinfunction "OUT_8") (pintype "output"))
      (node (ref "R15") (pin "2") (pinfunction "2_2") (pintype "passive"))
    )
    (net (code "60") (name "Net-(IC4D--IN)") (class "Default")
      (node (ref "C13") (pin "1") (pinfunction "1_1") (pintype "passive"))
      (node (ref "IC4") (pin "13") (pinfunction "-IN_13") (pintype "input"))
      (node (ref "R38") (pin "2") (pinfunction "2_2") (pintype "passive"))
      (node (ref "R46") (pin "1") (pinfunction "1_1") (pintype "passive"))
    )
    (net (code "61") (name "Net-(IC4D-OUT)") (class "Default")
      (node (ref "C13") (pin "2") (pinfunction "2_2") (pintype "passive"))
      (node (ref "IC4") (pin "14") (pinfunction "OUT_14") (pintype "output"))
      (node (ref "R14") (pin "2") (pinfunction "2_2") (pintype "passive"))
    )
    (net (code "62") (name "Net-(IC6A--IN)") (class "Default")
      (node (ref "C41") (pin "1") (pinfunction "1_1") (pintype "passive"))
      (node (ref "IC6") (pin "2") (pinfunction "-IN_2") (pintype "input"))
      (node (ref "R58") (pin "2") (pinfunction "2_2") (pintype "passive"))
      (node (ref "R65") (pin "1") (pinfunction "1_1") (pintype "passive"))
      (node (ref "R71") (pin "1") (pinfunction "1_1") (pintype "passive"))
    )
    (net (code "63") (name "Net-(IC6B--IN)") (class "Default")
      (node (ref "C42") (pin "1") (pinfunction "1_1") (pintype "passive"))
      (node (ref "IC6") (pin "6") (pinfunction "-IN_6") (pintype "input"))
      (node (ref "R59") (pin "2") (pinfunction "2_2") (pintype "passive"))
      (node (ref "R66") (pin "1") (pinfunction "1_1") (pintype "passive"))
      (node (ref "R72") (pin "1") (pinfunction "1_1") (pintype "passive"))
    )
    (net (code "64") (name "Net-(IC6C--IN)") (class "Default")
      (node (ref "C33") (pin "1") (pinfunction "1_1") (pintype "passive"))
      (node (ref "IC6") (pin "9") (pinfunction "-IN_9") (pintype "input"))
      (node (ref "R31") (pin "1") (pinfunction "1_1") (pintype "passive"))
      (node (ref "R32") (pin "1") (pinfunction "1_1") (pintype "passive"))
      (node (ref "R42") (pin "2") (pinfunction "2_2") (pintype "passive"))
    )
    (net (code "65") (name "Net-(IC6D--IN)") (class "Default")
      (node (ref "C32") (pin "1") (pinfunction "1_1") (pintype "passive"))
      (node (ref "IC6") (pin "13") (pinfunction "-IN_13") (pintype "input"))
      (node (ref "R29") (pin "1") (pinfunction "1_1") (pintype "passive"))
      (node (ref "R35") (pin "1") (pinfunction "1_1") (pintype "passive"))
      (node (ref "R41") (pin "2") (pinfunction "2_2") (pintype "passive"))
    )
    (net (code "66") (name "Net-(IC7-EN)") (class "Default")
      (node (ref "C26") (pin "1") (pinfunction "1_1") (pintype "passive"))
      (node (ref "IC7") (pin "1") (pinfunction "VIN_1") (pintype "bidirectional"))
      (node (ref "IC7") (pin "3") (pinfunction "EN_3") (pintype "bidirectional"))
      (node (ref "L3") (pin "1") (pinfunction "1_1") (pintype "passive"))
    )
    (net (code "67") (name "Net-(J1-3)") (class "Default")
      (node (ref "J1") (pin "P3") (pinfunction "3_P3") (pintype "passive"))
      (node (ref "R1") (pin "1") (pinfunction "1_1") (pintype "passive"))
    )
    (net (code "68") (name "Net-(J2-3)") (class "Default")
      (node (ref "J2") (pin "P3") (pinfunction "3_P3") (pintype "passive"))
      (node (ref "R2") (pin "1") (pinfunction "1_1") (pintype "passive"))
    )
    (net (code "69") (name "Net-(J3-3)") (class "Default")
      (node (ref "J3") (pin "P3") (pinfunction "3_P3") (pintype "passive"))
      (node (ref "R26") (pin "1") (pinfunction "1_1") (pintype "passive"))
    )
    (net (code "70") (name "Net-(J4-3)") (class "Default")
      (node (ref "J4") (pin "P3") (pinfunction "3_P3") (pintype "passive"))
      (node (ref "R65") (pin "2") (pinfunction "2_2") (pintype "passive"))
    )
    (net (code "71") (name "Net-(J5-3)") (class "Default")
      (node (ref "J5") (pin "P3") (pinfunction "3_P3") (pintype "passive"))
      (node (ref "R66") (pin "2") (pinfunction "2_2") (pintype "passive"))
    )
    (net (code "72") (name "Net-(J6-3)") (class "Default")
      (node (ref "J6") (pin "P3") (pinfunction "3_P3") (pintype "passive"))
      (node (ref "R32") (pin "2") (pinfunction "2_2") (pintype "passive"))
    )
    (net (code "73") (name "Net-(J7-3)") (class "Default")
      (node (ref "J7") (pin "P3") (pinfunction "3_P3") (pintype "passive"))
      (node (ref "R35") (pin "2") (pinfunction "2_2") (pintype "passive"))
    )
    (net (code "74") (name "Net-(J8-2)") (class "Default")
      (node (ref "J8") (pin "TIP") (pinfunction "2_TIP") (pintype "passive"))
      (node (ref "R28") (pin "1") (pinfunction "1_1") (pintype "passive"))
      (node (ref "R30") (pin "1") (pinfunction "1_1") (pintype "passive"))
    )
    (net (code "75") (name "Net-(J9-3)") (class "Default")
      (node (ref "J9") (pin "P3") (pinfunction "3_P3") (pintype "passive"))
      (node (ref "R27") (pin "1") (pinfunction "1_1") (pintype "passive"))
    )
    (net (code "76") (name "Net-(J10-2)") (class "Default")
      (node (ref "J10") (pin "TIP") (pinfunction "2_TIP") (pintype "passive"))
      (node (ref "R10") (pin "1") (pinfunction "1_1") (pintype "passive"))
      (node (ref "R11") (pin "1") (pinfunction "1_1") (pintype "passive"))
    )
    (net (code "77") (name "Net-(J11-2)") (class "Default")
      (node (ref "J11") (pin "TIP") (pinfunction "2_TIP") (pintype "passive"))
      (node (ref "R13") (pin "1") (pinfunction "1_1") (pintype "passive"))
      (node (ref "R8") (pin "1") (pinfunction "1_1") (pintype "passive"))
    )
    (net (code "78") (name "Net-(J12-2)") (class "Default")
      (node (ref "J12") (pin "TIP") (pinfunction "2_TIP") (pintype "passive"))
      (node (ref "R12") (pin "1") (pinfunction "1_1") (pintype "passive"))
      (node (ref "R9") (pin "1") (pinfunction "1_1") (pintype "passive"))
    )
    (net (code "79") (name "Net-(J13-2)") (class "Default")
      (node (ref "J13") (pin "TIP") (pinfunction "2_TIP") (pintype "passive"))
      (node (ref "R16") (pin "1") (pinfunction "1_1") (pintype "passive"))
      (node (ref "R34") (pin "1") (pinfunction "1_1") (pintype "passive"))
    )
    (net (code "80") (name "Net-(J14-2)") (class "Default")
      (node (ref "J14") (pin "TIP") (pinfunction "2_TIP") (pintype "passive"))
      (node (ref "R17") (pin "1") (pinfunction "1_1") (pintype "passive"))
      (node (ref "R33") (pin "1") (pinfunction "1_1") (pintype "passive"))
    )
    (net (code "81") (name "Net-(J15-2)") (class "Default")
      (node (ref "J15") (pin "TIP") (pinfunction "2_TIP") (pintype "passive"))
      (node (ref "R14") (pin "1") (pinfunction "1_1") (pintype "passive"))
      (node (ref "R38") (pin "1") (pinfunction "1_1") (pintype "passive"))
    )
    (net (code "82") (name "Net-(J16-2)") (class "Default")
      (node (ref "J16") (pin "TIP") (pinfunction "2_TIP") (pintype "passive"))
      (node (ref "R15") (pin "1") (pinfunction "1_1") (pintype "passive"))
      (node (ref "R36") (pin "1") (pinfunction "1_1") (pintype "passive"))
    )
    (net (code "83") (name "Net-(J19-RING)") (class "Default")
      (node (ref "J19") (pin "P$2") (pinfunction "RING_P$2") (pintype "bidirectional"))
      (node (ref "R39") (pin "1") (pinfunction "1_1") (pintype "passive"))
    )
    (net (code "84") (name "Net-(J19-TIP)") (class "Default")
      (node (ref "J19") (pin "P$3") (pinfunction "TIP_P$3") (pintype "bidirectional"))
      (node (ref "R40") (pin "1") (pinfunction "1_1") (pintype "passive"))
    )
    (net (code "85") (name "Net-(OK1-A)") (class "Default")
      (node (ref "OK1") (pin "2") (pinfunction "A_2") (pintype "passive"))
      (node (ref "R7") (pin "1") (pinfunction "1_1") (pintype "passive"))
    )
    (net (code "86") (name "Net-(Q1-PadB)") (class "Default")
      (node (ref "Q1") (pin "B") (pinfunction "B_B") (pintype "passive"))
      (node (ref "R1") (pin "2") (pinfunction "2_2") (pintype "passive"))
      (node (ref "R5") (pin "2") (pinfunction "2_2") (pintype "passive"))
    )
    (net (code "87") (name "Net-(Q2-PadB)") (class "Default")
      (node (ref "Q2") (pin "B") (pinfunction "B_B") (pintype "passive"))
      (node (ref "R24") (pin "2") (pinfunction "2_2") (pintype "passive"))
      (node (ref "R26") (pin "2") (pinfunction "2_2") (pintype "passive"))
    )
    (net (code "88") (name "Net-(Q3-PadB)") (class "Default")
      (node (ref "Q3") (pin "B") (pinfunction "B_B") (pintype "passive"))
      (node (ref "R25") (pin "2") (pinfunction "2_2") (pintype "passive"))
      (node (ref "R27") (pin "2") (pinfunction "2_2") (pintype "passive"))
    )
    (net (code "89") (name "Net-(Q4-PadB)") (class "Default")
      (node (ref "Q4") (pin "B") (pinfunction "B_B") (pintype "passive"))
      (node (ref "R2") (pin "2") (pinfunction "2_2") (pintype "passive"))
      (node (ref "R6") (pin "2") (pinfunction "2_2") (pintype "passive"))
    )
    (net (code "90") (name "VCC") (class "Default")
      (node (ref "C11") (pin "+") (pinfunction "+_+") (pintype "passive"))
      (node (ref "C19") (pin "1") (pinfunction "1_1") (pintype "passive"))
      (node (ref "C7") (pin "1") (pinfunction "1_1") (pintype "passive"))
      (node (ref "IC2") (pin "4") (pinfunction "V+_4") (pintype "power_in"))
      (node (ref "IC4") (pin "4") (pinfunction "V+_4") (pintype "power_in"))
      (node (ref "L2") (pin "1") (pinfunction "1_1") (pintype "passive"))
    )
    (net (code "91") (name "VEE") (class "Default")
      (node (ref "C20") (pin "2") (pinfunction "2_2") (pintype "passive"))
      (node (ref "C22") (pin "-") (pinfunction "-_-") (pintype "passive"))
      (node (ref "C8") (pin "2") (pinfunction "2_2") (pintype "passive"))
      (node (ref "IC2") (pin "11") (pinfunction "V-_11") (pintype "power_in"))
      (node (ref "IC4") (pin "11") (pinfunction "V-_11") (pintype "power_in"))
      (node (ref "L4") (pin "1") (pinfunction "1_1") (pintype "passive"))
      (node (ref "R68") (pin "1") (pinfunction "1_1") (pintype "passive"))
    )
    (net (code "92") (name "unconnected-(J1-2-PadP2)") (class "Default")
      (node (ref "J1") (pin "P2") (pinfunction "2_P2") (pintype "passive"))
    )
    (net (code "93") (name "unconnected-(J2-2-PadP2)") (class "Default")
      (node (ref "J2") (pin "P2") (pinfunction "2_P2") (pintype "passive"))
    )
    (net (code "94") (name "unconnected-(J3-2-PadP2)") (class "Default")
      (node (ref "J3") (pin "P2") (pinfunction "2_P2") (pintype "passive"))
    )
    (net (code "95") (name "unconnected-(J8-3-PadSW)") (class "Default")
      (node (ref "J8") (pin "SW") (pinfunction "3_SW") (pintype "passive"))
    )
    (net (code "96") (name "unconnected-(J9-2-PadP2)") (class "Default")
      (node (ref "J9") (pin "P2") (pinfunction "2_P2") (pintype "passive"))
    )
    (net (code "97") (name "unconnected-(J10-3-PadSW)") (class "Default")
      (node (ref "J10") (pin "SW") (pinfunction "3_SW") (pintype "passive"))
    )
    (net (code "98") (name "unconnected-(J11-3-PadSW)") (class "Default")
      (node (ref "J11") (pin "SW") (pinfunction "3_SW") (pintype "passive"))
    )
    (net (code "99") (name "unconnected-(J12-3-PadSW)") (class "Default")
      (node (ref "J12") (pin "SW") (pinfunction "3_SW") (pintype "passive"))
    )
    (net (code "100") (name "unconnected-(J13-3-PadSW)") (class "Default")
      (node (ref "J13") (pin "SW") (pinfunction "3_SW") (pintype "passive"))
    )
    (net (code "101") (name "unconnected-(J14-3-PadSW)") (class "Default")
      (node (ref "J14") (pin "SW") (pinfunction "3_SW") (pintype "passive"))
    )
    (net (code "102") (name "unconnected-(J15-3-PadSW)") (class "Default")
      (node (ref "J15") (pin "SW") (pinfunction "3_SW") (pintype "passive"))
    )
    (net (code "103") (name "unconnected-(J16-3-PadSW)") (class "Default")
      (node (ref "J16") (pin "SW") (pinfunction "3_SW") (pintype "passive"))
    )
    (net (code "104") (name "unconnected-(JP1-Pad2)") (class "Default")
      (node (ref "JP1") (pin "2") (pinfunction "2_2") (pintype "passive"))
    )
    (net (code "105") (name "unconnected-(JP1-Pad13)") (class "Default")
      (node (ref "JP1") (pin "13") (pinfunction "13_13") (pintype "passive"))
    )
    (net (code "106") (name "unconnected-(JP1-Pad16)") (class "Default")
      (node (ref "JP1") (pin "16") (pinfunction "16_16") (pintype "passive"))
    )
    (net (code "107") (name "unconnected-(JP1-Pad17)") (class "Default")
      (node (ref "JP1") (pin "17") (pinfunction "17_17") (pintype "passive"))
    )
    (net (code "108") (name "unconnected-(JP1-Pad18)") (class "Default")
      (node (ref "JP1") (pin "18") (pinfunction "18_18") (pintype "passive"))
    )
    (net (code "109") (name "unconnected-(JP2-Pad14)") (class "Default")
      (node (ref "JP2") (pin "14") (pinfunction "14_14") (pintype "passive"))
    )
    (net (code "110") (name "unconnected-(JP2-Pad17)") (class "Default")
      (node (ref "JP2") (pin "17") (pinfunction "17_17") (pintype "passive"))
    )
    (net (code "111") (name "unconnected-(JP2-Pad18)") (class "Default")
      (node (ref "JP2") (pin "18") (pinfunction "18_18") (pintype "passive"))
    )
    (net (code "112") (name "unconnected-(JP2-Pad19)") (class "Default")
      (node (ref "JP2") (pin "19") (pinfunction "19_19") (pintype "passive"))
    )
    (net (code "113") (name "unconnected-(JP3-Pad5)") (class "Default")
      (node (ref "JP3") (pin "5") (pinfunction "5_5") (pintype "passive"))
    )
    (net (code "114") (name "unconnected-(MODULE1-3V3-Pad1)") (class "Default")
      (node (ref "MODULE1") (pin "1") (pinfunction "3V3_1") (pintype "bidirectional"))
    )
    (net (code "115") (name "unconnected-(MODULE1-5V-Pad19)") (class "Default")
      (node (ref "MODULE1") (pin "19") (pinfunction "5V_19") (pintype "bidirectional"))
    )
    (net (code "116") (name "unconnected-(MODULE1-CLK-Pad20)") (class "Default")
      (node (ref "MODULE1") (pin "20") (pinfunction "CLK_20") (pintype "bidirectional"))
    )
    (net (code "117") (name "unconnected-(MODULE1-CMD-Pad18)") (class "Default")
      (node (ref "MODULE1") (pin "18") (pinfunction "CMD_18") (pintype "bidirectional"))
    )
    (net (code "118") (name "unconnected-(MODULE1-EN-Pad2)") (class "Default")
      (node (ref "MODULE1") (pin "2") (pinfunction "EN_2") (pintype "bidirectional"))
    )
    (net (code "119") (name "unconnected-(MODULE1-GND-Pad14)") (class "Default")
      (node (ref "MODULE1") (pin "14") (pinfunction "GND_14") (pintype "bidirectional"))
    )
    (net (code "120") (name "unconnected-(MODULE1-GND-Pad32)") (class "Default")
      (node (ref "MODULE1") (pin "32") (pinfunction "GND_32") (pintype "bidirectional"))
    )
    (net (code "121") (name "unconnected-(MODULE1-GND-Pad38)") (class "Default")
      (node (ref "MODULE1") (pin "38") (pinfunction "GND_38") (pintype "bidirectional"))
    )
    (net (code "122") (name "unconnected-(MODULE1-IO0-Pad25)") (class "Default")
      (node (ref "MODULE1") (pin "25") (pinfunction "IO0_25") (pintype "bidirectional"))
    )
    (net (code "123") (name "unconnected-(MODULE1-IO2-Pad24)") (class "Default")
      (node (ref "MODULE1") (pin "24") (pinfunction "IO2_24") (pintype "bidirectional"))
    )
    (net (code "124") (name "unconnected-(MODULE1-IO4-Pad26)") (class "Default")
      (node (ref "MODULE1") (pin "26") (pinfunction "IO4_26") (pintype "bidirectional"))
    )
    (net (code "125") (name "unconnected-(MODULE1-IO5-Pad29)") (class "Default")
      (node (ref "MODULE1") (pin "29") (pinfunction "IO5_29") (pintype "bidirectional"))
    )
    (net (code "126") (name "unconnected-(MODULE1-IO12-Pad13)") (class "Default")
      (node (ref "MODULE1") (pin "13") (pinfunction "IO12_13") (pintype "bidirectional"))
    )
    (net (code "127") (name "unconnected-(MODULE1-IO13-Pad15)") (class "Default")
      (node (ref "MODULE1") (pin "15") (pinfunction "IO13_15") (pintype "bidirectional"))
    )
    (net (code "128") (name "unconnected-(MODULE1-IO14-Pad12)") (class "Default")
      (node (ref "MODULE1") (pin "12") (pinfunction "IO14_12") (pintype "bidirectional"))
    )
    (net (code "129") (name "unconnected-(MODULE1-IO15-Pad23)") (class "Default")
      (node (ref "MODULE1") (pin "23") (pinfunction "IO15_23") (pintype "bidirectional"))
    )
    (net (code "130") (name "unconnected-(MODULE1-IO16-Pad27)") (class "Default")
      (node (ref "MODULE1") (pin "27") (pinfunction "IO16_27") (pintype "bidirectional"))
    )
    (net (code "131") (name "unconnected-(MODULE1-IO17-Pad28)") (class "Default")
      (node (ref "MODULE1") (pin "28") (pinfunction "IO17_28") (pintype "bidirectional"))
    )
    (net (code "132") (name "unconnected-(MODULE1-IO18-Pad30)") (class "Default")
      (node (ref "MODULE1") (pin "30") (pinfunction "IO18_30") (pintype "bidirectional"))
    )
    (net (code "133") (name "unconnected-(MODULE1-IO19-Pad31)") (class "Default")
      (node (ref "MODULE1") (pin "31") (pinfunction "IO19_31") (pintype "bidirectional"))
    )
    (net (code "134") (name "unconnected-(MODULE1-IO21-Pad33)") (class "Default")
      (node (ref "MODULE1") (pin "33") (pinfunction "IO21_33") (pintype "bidirectional"))
    )
    (net (code "135") (name "unconnected-(MODULE1-IO22-Pad36)") (class "Default")
      (node (ref "MODULE1") (pin "36") (pinfunction "IO22_36") (pintype "bidirectional"))
    )
    (net (code "136") (name "unconnected-(MODULE1-IO23-Pad37)") (class "Default")
      (node (ref "MODULE1") (pin "37") (pinfunction "IO23_37") (pintype "bidirectional"))
    )
    (net (code "137") (name "unconnected-(MODULE1-IO25-Pad9)") (class "Default")
      (node (ref "MODULE1") (pin "9") (pinfunction "IO25_9") (pintype "bidirectional"))
    )
    (net (code "138") (name "unconnected-(MODULE1-IO26-Pad10)") (class "Default")
      (node (ref "MODULE1") (pin "10") (pinfunction "IO26_10") (pintype "bidirectional"))
    )
    (net (code "139") (name "unconnected-(MODULE1-IO27-Pad11)") (class "Default")
      (node (ref "MODULE1") (pin "11") (pinfunction "IO27_11") (pintype "bidirectional"))
    )
    (net (code "140") (name "unconnected-(MODULE1-IO32-Pad7)") (class "Default")
      (node (ref "MODULE1") (pin "7") (pinfunction "IO32_7") (pintype "bidirectional"))
    )
    (net (code "141") (name "unconnected-(MODULE1-IO33-Pad8)") (class "Default")
      (node (ref "MODULE1") (pin "8") (pinfunction "IO33_8") (pintype "bidirectional"))
    )
    (net (code "142") (name "unconnected-(MODULE1-IO34-Pad5)") (class "Default")
      (node (ref "MODULE1") (pin "5") (pinfunction "IO34_5") (pintype "bidirectional"))
    )
    (net (code "143") (name "unconnected-(MODULE1-IO35-Pad6)") (class "Default")
      (node (ref "MODULE1") (pin "6") (pinfunction "IO35_6") (pintype "bidirectional"))
    )
    (net (code "144") (name "unconnected-(MODULE1-RXD0-Pad34)") (class "Default")
      (node (ref "MODULE1") (pin "34") (pinfunction "RXD0_34") (pintype "bidirectional"))
    )
    (net (code "145") (name "unconnected-(MODULE1-SD0-Pad21)") (class "Default")
      (node (ref "MODULE1") (pin "21") (pinfunction "SD0_21") (pintype "bidirectional"))
    )
    (net (code "146") (name "unconnected-(MODULE1-SD1-Pad22)") (class "Default")
      (node (ref "MODULE1") (pin "22") (pinfunction "SD1_22") (pintype "bidirectional"))
    )
    (net (code "147") (name "unconnected-(MODULE1-SD2-Pad16)") (class "Default")
      (node (ref "MODULE1") (pin "16") (pinfunction "SD2_16") (pintype "bidirectional"))
    )
    (net (code "148") (name "unconnected-(MODULE1-SD3-Pad17)") (class "Default")
      (node (ref "MODULE1") (pin "17") (pinfunction "SD3_17") (pintype "bidirectional"))
    )
    (net (code "149") (name "unconnected-(MODULE1-SVN-Pad4)") (class "Default")
      (node (ref "MODULE1") (pin "4") (pinfunction "SVN_4") (pintype "bidirectional"))
    )
    (net (code "150") (name "unconnected-(MODULE1-SVP-Pad3)") (class "Default")
      (node (ref "MODULE1") (pin "3") (pinfunction "SVP_3") (pintype "bidirectional"))
    )
    (net (code "151") (name "unconnected-(MODULE1-TXD0-Pad35)") (class "Default")
      (node (ref "MODULE1") (pin "35") (pinfunction "TXD0_35") (pintype "bidirectional"))
    )
    (net (code "152") (name "unconnected-(OK1-VE-Pad7)") (class "Default")
      (node (ref "OK1") (pin "7") (pinfunction "VE_7") (pintype "passive"))
    )
  )
)
